# Timelapse_camera_RevB.net
KiCad netlist of a schematic drawn in EAGLE
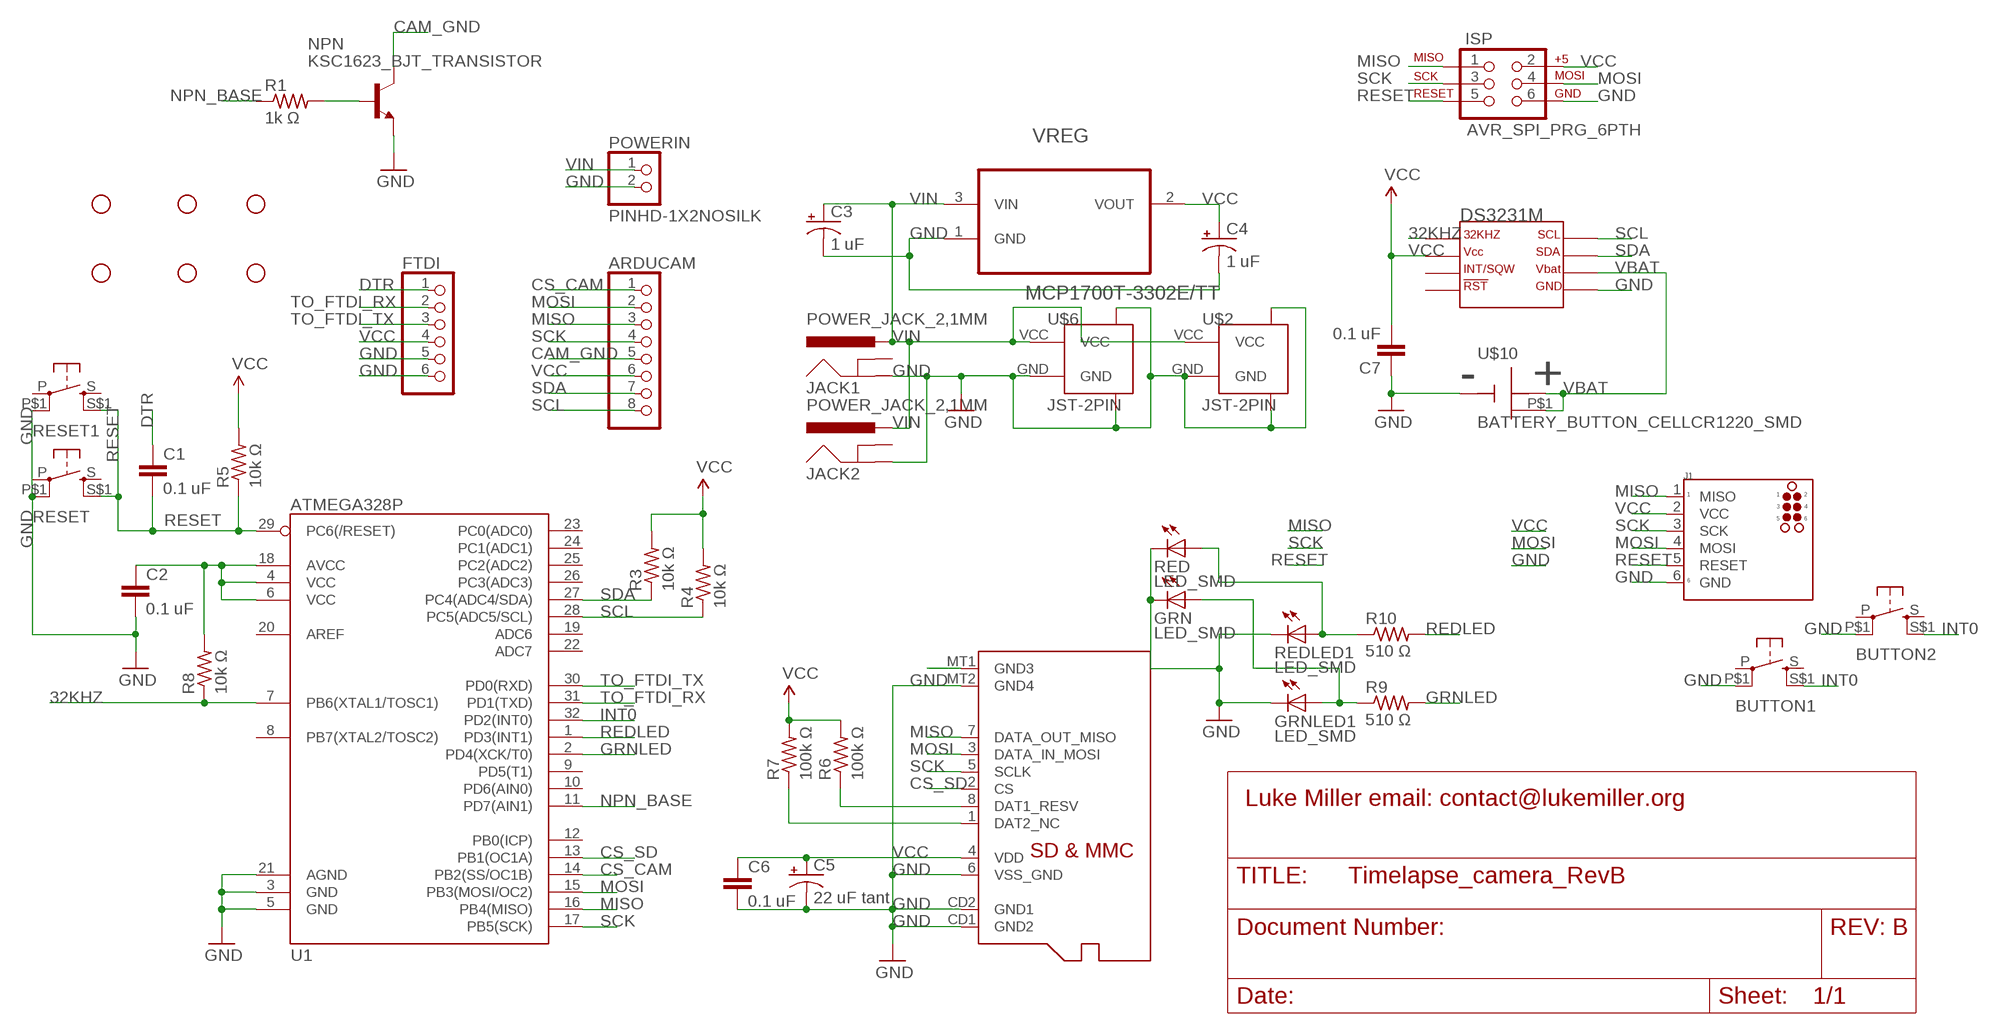
[diagram p0: schematic, sheet 1]

(export (version "E")
  (design (tool "Eeschema 10.0.6"))
  (components
    (comp (ref "ARDUCAM")
      (value "PINHD-1X8RIGHTANGLE_FEMALE")
      (footprint "eagle-import:1X08-RA")
      (libsource (lib "eagle-import") (part "PINHD-1X8RIGHTANGLE_FEMALE"))
    )
    (comp (ref "BUTTON1")
      (value "PUSHBUTTON_DPST_SMDSTANDARD")
      (footprint "eagle-import:PUSHBUTTON_DPST_SMD")
      (libsource (lib "eagle-import") (part "PUSHBUTTON_DPST_SMDSTANDARD"))
    )
    (comp (ref "BUTTON2")
      (value "PUSHBUTTON_DPST_SMDSTANDARD")
      (footprint "eagle-import:PUSHBUTTON_DPST_SMD")
      (libsource (lib "eagle-import") (part "PUSHBUTTON_DPST_SMDSTANDARD"))
    )
    (comp (ref "C1")
      (value "0.1 uF")
      (footprint "eagle-import:0805")
      (libsource (lib "eagle-import") (part "CAP0805"))
    )
    (comp (ref "C2")
      (value "0.1 uF")
      (footprint "eagle-import:0805")
      (libsource (lib "eagle-import") (part "CAP0805"))
    )
    (comp (ref "C3")
      (value "1 uF")
      (footprint "eagle-import:PANASONIC_B")
      (libsource (lib "eagle-import") (part "CPOL-USB"))
    )
    (comp (ref "C4")
      (value "1 uF")
      (footprint "eagle-import:PANASONIC_B")
      (libsource (lib "eagle-import") (part "CPOL-USB"))
    )
    (comp (ref "C5")
      (value "22 uF tant")
      (footprint "eagle-import:C0805_POL")
      (libsource (lib "eagle-import") (part "CPOL-US0805"))
    )
    (comp (ref "C6")
      (value "0.1 uF")
      (footprint "eagle-import:0805")
      (libsource (lib "eagle-import") (part "CAP0805"))
    )
    (comp (ref "C7")
      (value "0.1 uF")
      (footprint "eagle-import:0805")
      (libsource (lib "eagle-import") (part "CAP0805"))
    )
    (comp (ref "DS3231M")
      (value "DS3231MSOIC-8")
      (footprint "eagle-import:DS3231M_SOIC8")
      (libsource (lib "eagle-import") (part "DS3231MSOIC-8"))
    )
    (comp (ref "FTDI")
      (value "PINHD-1X6CB")
      (footprint "eagle-import:1X06-CLEANBIG")
      (libsource (lib "eagle-import") (part "PINHD-1X6CB"))
    )
    (comp (ref "GRN")
      (value "LED_SMD")
      (footprint "eagle-import:CHIPLED_0805")
      (libsource (lib "eagle-import") (part "LED_SMD"))
    )
    (comp (ref "GRNLED1")
      (value "LED_SMD")
      (footprint "eagle-import:CHIPLED_0805")
      (libsource (lib "eagle-import") (part "LED_SMD"))
    )
    (comp (ref "ISP")
      (value "AVR_SPI_PRG_6PTH")
      (footprint "eagle-import:2X3")
      (libsource (lib "eagle-import") (part "AVR_SPI_PRG_6PTH"))
    )
    (comp (ref "J1")
      (value "TC2030-MCP-NL")
      (footprint "eagle-import:TC2030-MCP-NL")
      (libsource (lib "eagle-import") (part "TC2030-MCP-NL"))
    )
    (comp (ref "JACK1")
      (value "POWER_JACK_2,1MM")
      (footprint "eagle-import:POWER_JACK_DC_2,1MM")
      (libsource (lib "eagle-import") (part "POWER_JACK_2,1MM"))
    )
    (comp (ref "JACK2")
      (value "POWER_JACK_2,1MM")
      (footprint "eagle-import:POWER_JACK_DC_2,1MM")
      (libsource (lib "eagle-import") (part "POWER_JACK_2,1MM"))
    )
    (comp (ref "NPN")
      (value "KSC1623_BJT_TRANSISTOR")
      (footprint "eagle-import:SOT23")
      (libsource (lib "eagle-import") (part "KSC1623_BJT_TRANSISTOR"))
    )
    (comp (ref "POWERIN")
      (value "PINHD-1X2NOSILK")
      (footprint "eagle-import:1X02_NOSILK")
      (libsource (lib "eagle-import") (part "PINHD-1X2NOSILK"))
    )
    (comp (ref "R1")
      (value "1k Ω")
      (footprint "eagle-import:R0805")
      (libsource (lib "eagle-import") (part "RESISTOR_SMDR0805"))
    )
    (comp (ref "R3")
      (value "10k Ω")
      (footprint "eagle-import:R0805")
      (libsource (lib "eagle-import") (part "RESISTOR_SMDR0805"))
    )
    (comp (ref "R4")
      (value "10k Ω")
      (footprint "eagle-import:R0805")
      (libsource (lib "eagle-import") (part "RESISTOR_SMDR0805"))
    )
    (comp (ref "R5")
      (value "10k Ω")
      (footprint "eagle-import:R0805")
      (libsource (lib "eagle-import") (part "RESISTOR_SMDR0805"))
    )
    (comp (ref "R6")
      (value "100k Ω")
      (footprint "eagle-import:R0805")
      (libsource (lib "eagle-import") (part "RESISTOR_SMDR0805"))
    )
    (comp (ref "R7")
      (value "100k Ω")
      (footprint "eagle-import:R0805")
      (libsource (lib "eagle-import") (part "RESISTOR_SMDR0805"))
    )
    (comp (ref "R8")
      (value "10k Ω")
      (footprint "eagle-import:R0805")
      (libsource (lib "eagle-import") (part "RESISTOR_SMDR0805"))
    )
    (comp (ref "R9")
      (value "510 Ω")
      (footprint "eagle-import:R0805")
      (libsource (lib "eagle-import") (part "RESISTOR_SMDR0805"))
    )
    (comp (ref "R10")
      (value "510 Ω")
      (footprint "eagle-import:R0805")
      (libsource (lib "eagle-import") (part "RESISTOR_SMDR0805"))
    )
    (comp (ref "RED")
      (value "LED_SMD")
      (footprint "eagle-import:CHIPLED_0805")
      (libsource (lib "eagle-import") (part "LED_SMD"))
    )
    (comp (ref "REDLED1")
      (value "LED_SMD")
      (footprint "eagle-import:CHIPLED_0805")
      (libsource (lib "eagle-import") (part "LED_SMD"))
    )
    (comp (ref "RESET")
      (value "PUSHBUTTON_DPST_SMDSTANDARD")
      (footprint "eagle-import:PUSHBUTTON_DPST_SMD")
      (libsource (lib "eagle-import") (part "PUSHBUTTON_DPST_SMDSTANDARD"))
    )
    (comp (ref "RESET1")
      (value "PUSHBUTTON_DPST_SMDSTANDARD")
      (footprint "eagle-import:PUSHBUTTON_DPST_SMD")
      (libsource (lib "eagle-import") (part "PUSHBUTTON_DPST_SMDSTANDARD"))
    )
    (comp (ref "STANDOFF1")
      (value "STAND-OFF")
      (footprint "eagle-import:STAND-OFF")
      (libsource (lib "eagle-import") (part "STAND-OFF"))
    )
    (comp (ref "STANDOFF2")
      (value "STAND-OFF")
      (footprint "eagle-import:STAND-OFF")
      (libsource (lib "eagle-import") (part "STAND-OFF"))
    )
    (comp (ref "STANDOFF3")
      (value "STAND-OFF")
      (footprint "eagle-import:STAND-OFF")
      (libsource (lib "eagle-import") (part "STAND-OFF"))
    )
    (comp (ref "STANDOFF4")
      (value "STAND-OFF")
      (footprint "eagle-import:STAND-OFF")
      (libsource (lib "eagle-import") (part "STAND-OFF"))
    )
    (comp (ref "STANDOFF5")
      (value "STAND-OFF")
      (footprint "eagle-import:STAND-OFF")
      (libsource (lib "eagle-import") (part "STAND-OFF"))
    )
    (comp (ref "STANDOFF6")
      (value "STAND-OFF")
      (footprint "eagle-import:STAND-OFF")
      (libsource (lib "eagle-import") (part "STAND-OFF"))
    )
    (comp (ref "U$2")
      (value "JST-2PIN")
      (footprint "eagle-import:JST-2-SMD-VERT")
      (libsource (lib "eagle-import") (part "JST-2PIN"))
    )
    (comp (ref "U$3")
      (value "MICROSD")
      (footprint "eagle-import:MICROSD")
      (libsource (lib "eagle-import") (part "MICROSD"))
    )
    (comp (ref "U$6")
      (value "JST-2PIN")
      (footprint "eagle-import:JST-2-SMD-VERT")
      (libsource (lib "eagle-import") (part "JST-2PIN"))
    )
    (comp (ref "U$10")
      (value "BATTERY_BUTTON_CELLCR1220_SMD")
      (footprint "eagle-import:CR1220_BATTERY_HOLDER_SMD")
      (libsource (lib "eagle-import") (part "BATTERY_BUTTON_CELLCR1220_SMD"))
    )
    (comp (ref "U1")
      (value "ATMEGA328P")
      (footprint "eagle-import:TQFP32-08")
      (libsource (lib "eagle-import") (part "ATMEGA328_SMT"))
    )
    (comp (ref "VREG")
      (value "MCP1700T-3302E/TT")
      (footprint "eagle-import:SOT95P237X112-3N")
      (libsource (lib "eagle-import") (part "MCP1700T-3302E/TT"))
    )
  )
  (nets
    (net (code "1") (name "/32KHZ") (class "Default")
      (node (ref "DS3231M") (pin "1") (pinfunction "P$1_32KHZ_1") (pintype "bidirectional"))
      (node (ref "R8") (pin "1") (pinfunction "1_1") (pintype "passive"))
      (node (ref "U1") (pin "7") (pinfunction "PB6(XTAL1/TOSC1)_7") (pintype "bidirectional"))
    )
    (net (code "2") (name "/CAM_GND") (class "Default")
      (node (ref "ARDUCAM") (pin "5") (pinfunction "5_5") (pintype "passive"))
      (node (ref "NPN") (pin "3") (pinfunction "C_3") (pintype "passive"))
    )
    (net (code "3") (name "/CS_CAM") (class "Default")
      (node (ref "ARDUCAM") (pin "1") (pinfunction "1_1") (pintype "passive"))
      (node (ref "U1") (pin "14") (pinfunction "PB2(SS/OC1B)_14") (pintype "bidirectional"))
    )
    (net (code "4") (name "/CS_SD") (class "Default")
      (node (ref "U$3") (pin "2") (pinfunction "CS_2") (pintype "input"))
      (node (ref "U1") (pin "13") (pinfunction "PB1(OC1A)_13") (pintype "bidirectional"))
    )
    (net (code "5") (name "/DTR") (class "Default")
      (node (ref "C1") (pin "1") (pinfunction "1_1") (pintype "passive"))
      (node (ref "FTDI") (pin "1") (pinfunction "1_1") (pintype "passive"))
    )
    (net (code "6") (name "/GRNLED") (class "Default")
      (node (ref "R9") (pin "2") (pinfunction "2_2") (pintype "passive"))
      (node (ref "U1") (pin "2") (pinfunction "PD4(XCK/T0)_2") (pintype "bidirectional"))
    )
    (net (code "7") (name "/INT0") (class "Default")
      (node (ref "BUTTON1") (pin "S$1") (pinfunction "S1_S$1") (pintype "passive"))
      (node (ref "BUTTON2") (pin "S$1") (pinfunction "S1_S$1") (pintype "passive"))
      (node (ref "U1") (pin "32") (pinfunction "PD2(INT0)_32") (pintype "bidirectional"))
    )
    (net (code "8") (name "/MISO") (class "Default")
      (node (ref "ARDUCAM") (pin "3") (pinfunction "3_3") (pintype "passive"))
      (node (ref "ISP") (pin "1") (pinfunction "1_1") (pintype "passive"))
      (node (ref "J1") (pin "1") (pinfunction "MISO_1") (pintype "bidirectional"))
      (node (ref "U$3") (pin "7") (pinfunction "DATA_OUT_MISO_7") (pintype "output"))
      (node (ref "U1") (pin "16") (pinfunction "PB4(MISO)_16") (pintype "bidirectional"))
    )
    (net (code "9") (name "/MOSI") (class "Default")
      (node (ref "ARDUCAM") (pin "2") (pinfunction "2_2") (pintype "passive"))
      (node (ref "ISP") (pin "4") (pinfunction "4_4") (pintype "passive"))
      (node (ref "J1") (pin "4") (pinfunction "MOSI_4") (pintype "bidirectional"))
      (node (ref "U$3") (pin "3") (pinfunction "DATA_IN_MOSI_3") (pintype "input"))
      (node (ref "U1") (pin "15") (pinfunction "PB3(MOSI/OC2)_15") (pintype "bidirectional"))
    )
    (net (code "10") (name "/NPN_BASE") (class "Default")
      (node (ref "R1") (pin "1") (pinfunction "1_1") (pintype "passive"))
      (node (ref "U1") (pin "11") (pinfunction "PD7(AIN1)_11") (pintype "bidirectional"))
    )
    (net (code "11") (name "/REDLED") (class "Default")
      (node (ref "R10") (pin "2") (pinfunction "2_2") (pintype "passive"))
      (node (ref "U1") (pin "1") (pinfunction "PD3(INT1)_1") (pintype "bidirectional"))
    )
    (net (code "12") (name "/RESET") (class "Default")
      (node (ref "C1") (pin "2") (pinfunction "2_2") (pintype "passive"))
      (node (ref "ISP") (pin "5") (pinfunction "5_5") (pintype "passive"))
      (node (ref "J1") (pin "5") (pinfunction "RESET_5") (pintype "bidirectional"))
      (node (ref "R5") (pin "1") (pinfunction "1_1") (pintype "passive"))
      (node (ref "RESET") (pin "S$1") (pinfunction "S1_S$1") (pintype "passive"))
      (node (ref "RESET1") (pin "S$1") (pinfunction "S1_S$1") (pintype "passive"))
      (node (ref "U1") (pin "29") (pinfunction "PC6(/RESET)_29") (pintype "bidirectional"))
    )
    (net (code "13") (name "/SCK") (class "Default")
      (node (ref "ARDUCAM") (pin "4") (pinfunction "4_4") (pintype "passive"))
      (node (ref "ISP") (pin "3") (pinfunction "3_3") (pintype "passive"))
      (node (ref "J1") (pin "3") (pinfunction "SCK_3") (pintype "bidirectional"))
      (node (ref "U$3") (pin "5") (pinfunction "SCLK_5") (pintype "input"))
      (node (ref "U1") (pin "17") (pinfunction "PB5(SCK)_17") (pintype "bidirectional"))
    )
    (net (code "14") (name "/SCL") (class "Default")
      (node (ref "ARDUCAM") (pin "8") (pinfunction "8_8") (pintype "passive"))
      (node (ref "DS3231M") (pin "8") (pinfunction "P$8_SCL_8") (pintype "bidirectional"))
      (node (ref "R4") (pin "1") (pinfunction "1_1") (pintype "passive"))
      (node (ref "U1") (pin "28") (pinfunction "PC5(ADC5/SCL)_28") (pintype "bidirectional"))
    )
    (net (code "15") (name "/SDA") (class "Default")
      (node (ref "ARDUCAM") (pin "7") (pinfunction "7_7") (pintype "passive"))
      (node (ref "DS3231M") (pin "7") (pinfunction "P$7_SDA_7") (pintype "bidirectional"))
      (node (ref "R3") (pin "1") (pinfunction "1_1") (pintype "passive"))
      (node (ref "U1") (pin "27") (pinfunction "PC4(ADC4/SDA)_27") (pintype "bidirectional"))
    )
    (net (code "16") (name "/TO_FTDI_RX") (class "Default")
      (node (ref "FTDI") (pin "2") (pinfunction "2_2") (pintype "passive"))
      (node (ref "U1") (pin "31") (pinfunction "PD1(TXD)_31") (pintype "bidirectional"))
    )
    (net (code "17") (name "/TO_FTDI_TX") (class "Default")
      (node (ref "FTDI") (pin "3") (pinfunction "3_3") (pintype "passive"))
      (node (ref "U1") (pin "30") (pinfunction "PD0(RXD)_30") (pintype "bidirectional"))
    )
    (net (code "18") (name "/VBAT") (class "Default")
      (node (ref "DS3231M") (pin "6") (pinfunction "P$6_VBAT_6") (pintype "bidirectional"))
      (node (ref "U$10") (pin "P$1") (pinfunction "P$2_VBAT_P$1") (pintype "power_in"))
      (node (ref "U$10") (pin "P$2") (pinfunction "VBAT_P$2") (pintype "power_in"))
    )
    (net (code "19") (name "/VIN") (class "Default")
      (node (ref "C3") (pin "+") (pinfunction "+_+") (pintype "passive"))
      (node (ref "JACK1") (pin "P$1") (pinfunction "PWR_P$1") (pintype "bidirectional"))
      (node (ref "JACK2") (pin "P$1") (pinfunction "PWR_P$1") (pintype "bidirectional"))
      (node (ref "POWERIN") (pin "1") (pinfunction "1_1") (pintype "passive"))
      (node (ref "U$2") (pin "VCC") (pinfunction "VCC_VCC") (pintype "power_in"))
      (node (ref "U$6") (pin "VCC") (pinfunction "VCC_VCC") (pintype "power_in"))
      (node (ref "VREG") (pin "3") (pinfunction "VIN_3") (pintype "input"))
    )
    (net (code "20") (name "GND") (class "Default")
      (node (ref "BUTTON1") (pin "P$1") (pinfunction "P1_P$1") (pintype "passive"))
      (node (ref "BUTTON2") (pin "P$1") (pinfunction "P1_P$1") (pintype "passive"))
      (node (ref "C2") (pin "2") (pinfunction "2_2") (pintype "passive"))
      (node (ref "C3") (pin "-") (pinfunction "-_-") (pintype "passive"))
      (node (ref "C4") (pin "-") (pinfunction "-_-") (pintype "passive"))
      (node (ref "C5") (pin "P$2_C") (pinfunction "-_P$2_C") (pintype "passive"))
      (node (ref "C6") (pin "2") (pinfunction "2_2") (pintype "passive"))
      (node (ref "C7") (pin "1") (pinfunction "1_1") (pintype "passive"))
      (node (ref "DS3231M") (pin "5") (pinfunction "P$5_GND_5") (pintype "power_in"))
      (node (ref "FTDI") (pin "5") (pinfunction "5_5") (pintype "passive"))
      (node (ref "FTDI") (pin "6") (pinfunction "6_6") (pintype "passive"))
      (node (ref "GRN") (pin "C") (pinfunction "C_C") (pintype "passive"))
      (node (ref "GRNLED1") (pin "C") (pinfunction "C_C") (pintype "passive"))
      (node (ref "ISP") (pin "6") (pinfunction "6_6") (pintype "passive"))
      (node (ref "J1") (pin "6") (pinfunction "GND_6") (pintype "power_in"))
      (node (ref "JACK1") (pin "P$2") (pinfunction "GND_P$2") (pintype "bidirectional"))
      (node (ref "JACK2") (pin "P$2") (pinfunction "GND_P$2") (pintype "bidirectional"))
      (node (ref "NPN") (pin "2") (pinfunction "E_2") (pintype "passive"))
      (node (ref "POWERIN") (pin "2") (pinfunction "2_2") (pintype "passive"))
      (node (ref "RED") (pin "C") (pinfunction "C_C") (pintype "passive"))
      (node (ref "REDLED1") (pin "C") (pinfunction "C_C") (pintype "passive"))
      (node (ref "RESET") (pin "P$1") (pinfunction "P1_P$1") (pintype "passive"))
      (node (ref "RESET1") (pin "P$1") (pinfunction "P1_P$1") (pintype "passive"))
      (node (ref "U$10") (pin "GND") (pinfunction "GND_GND") (pintype "power_in"))
      (node (ref "U$2") (pin "GND") (pinfunction "GND_GND") (pintype "power_in"))
      (node (ref "U$2") (pin "P$1") (pinfunction "BODY1_P$1") (pintype "power_in"))
      (node (ref "U$2") (pin "P$2") (pinfunction "BODY2_P$2") (pintype "power_in"))
      (node (ref "U$3") (pin "6") (pinfunction "VSS_GND_6") (pintype "power_in"))
      (node (ref "U$3") (pin "CD1") (pinfunction "GND2_CD1") (pintype "power_in"))
      (node (ref "U$3") (pin "CD2") (pinfunction "GND1_CD2") (pintype "power_in"))
      (node (ref "U$3") (pin "MT2") (pinfunction "GND4_MT2") (pintype "passive"))
      (node (ref "U$6") (pin "GND") (pinfunction "GND_GND") (pintype "power_in"))
      (node (ref "U$6") (pin "P$1") (pinfunction "BODY1_P$1") (pintype "power_in"))
      (node (ref "U$6") (pin "P$2") (pinfunction "BODY2_P$2") (pintype "power_in"))
      (node (ref "U1") (pin "21") (pinfunction "AGND_21") (pintype "bidirectional"))
      (node (ref "U1") (pin "3") (pinfunction "GND_3") (pintype "bidirectional"))
      (node (ref "U1") (pin "5") (pinfunction "GND_5") (pintype "bidirectional"))
      (node (ref "VREG") (pin "1") (pinfunction "GND_1") (pintype "passive"))
    )
    (net (code "21") (name "Net-(GRN-PadA)") (class "Default")
      (node (ref "GRN") (pin "A") (pinfunction "A_A") (pintype "passive"))
      (node (ref "GRNLED1") (pin "A") (pinfunction "A_A") (pintype "passive"))
      (node (ref "R9") (pin "1") (pinfunction "1_1") (pintype "passive"))
    )
    (net (code "22") (name "Net-(NPN-B)") (class "Default")
      (node (ref "NPN") (pin "1") (pinfunction "B_1") (pintype "passive"))
      (node (ref "R1") (pin "2") (pinfunction "2_2") (pintype "passive"))
    )
    (net (code "23") (name "Net-(R10-Pad1)") (class "Default")
      (node (ref "R10") (pin "1") (pinfunction "1_1") (pintype "passive"))
      (node (ref "RED") (pin "A") (pinfunction "A_A") (pintype "passive"))
      (node (ref "REDLED1") (pin "A") (pinfunction "A_A") (pintype "passive"))
    )
    (net (code "24") (name "Net-(U$3-DAT1_RESV)") (class "Default")
      (node (ref "R6") (pin "1") (pinfunction "1_1") (pintype "passive"))
      (node (ref "U$3") (pin "8") (pinfunction "DAT1_RESV_8") (pintype "bidirectional"))
    )
    (net (code "25") (name "Net-(U$3-DAT2_NC)") (class "Default")
      (node (ref "R7") (pin "1") (pinfunction "1_1") (pintype "passive"))
      (node (ref "U$3") (pin "1") (pinfunction "DAT2_NC_1") (pintype "bidirectional"))
    )
    (net (code "26") (name "VCC") (class "Default")
      (node (ref "ARDUCAM") (pin "6") (pinfunction "6_6") (pintype "passive"))
      (node (ref "C2") (pin "1") (pinfunction "1_1") (pintype "passive"))
      (node (ref "C4") (pin "+") (pinfunction "+_+") (pintype "passive"))
      (node (ref "C5") (pin "P$1_A") (pinfunction "+_P$1_A") (pintype "passive"))
      (node (ref "C6") (pin "1") (pinfunction "1_1") (pintype "passive"))
      (node (ref "C7") (pin "2") (pinfunction "2_2") (pintype "passive"))
      (node (ref "DS3231M") (pin "2") (pinfunction "P$2_VCC_2") (pintype "power_in"))
      (node (ref "FTDI") (pin "4") (pinfunction "4_4") (pintype "passive"))
      (node (ref "ISP") (pin "2") (pinfunction "2_2") (pintype "passive"))
      (node (ref "J1") (pin "2") (pinfunction "VCC_2") (pintype "power_in"))
      (node (ref "R3") (pin "2") (pinfunction "2_2") (pintype "passive"))
      (node (ref "R4") (pin "2") (pinfunction "2_2") (pintype "passive"))
      (node (ref "R5") (pin "2") (pinfunction "2_2") (pintype "passive"))
      (node (ref "R6") (pin "2") (pinfunction "2_2") (pintype "passive"))
      (node (ref "R7") (pin "2") (pinfunction "2_2") (pintype "passive"))
      (node (ref "R8") (pin "2") (pinfunction "2_2") (pintype "passive"))
      (node (ref "U$3") (pin "4") (pinfunction "VDD_4") (pintype "power_in"))
      (node (ref "U1") (pin "18") (pinfunction "AVCC_18") (pintype "bidirectional"))
      (node (ref "U1") (pin "4") (pinfunction "VCC_4") (pintype "bidirectional"))
      (node (ref "U1") (pin "6") (pinfunction "VCC_6") (pintype "bidirectional"))
      (node (ref "VREG") (pin "2") (pinfunction "VOUT_2") (pintype "output"))
    )
    (net (code "27") (name "unconnected-(BUTTON1-PadP)") (class "Default")
      (node (ref "BUTTON1") (pin "P") (pinfunction "P_P") (pintype "passive"))
    )
    (net (code "28") (name "unconnected-(BUTTON1-PadS)") (class "Default")
      (node (ref "BUTTON1") (pin "S") (pinfunction "S_S") (pintype "passive"))
    )
    (net (code "29") (name "unconnected-(BUTTON2-PadP)") (class "Default")
      (node (ref "BUTTON2") (pin "P") (pinfunction "P_P") (pintype "passive"))
    )
    (net (code "30") (name "unconnected-(BUTTON2-PadS)") (class "Default")
      (node (ref "BUTTON2") (pin "S") (pinfunction "S_S") (pintype "passive"))
    )
    (net (code "31") (name "unconnected-(DS3231M-P$3_INT-Pad3)") (class "Default")
      (node (ref "DS3231M") (pin "3") (pinfunction "P$3_INT_3") (pintype "bidirectional"))
    )
    (net (code "32") (name "unconnected-(DS3231M-P$4_RST-Pad4)") (class "Default")
      (node (ref "DS3231M") (pin "4") (pinfunction "P$4_RST_4") (pintype "bidirectional"))
    )
    (net (code "33") (name "unconnected-(JACK1-GNDBREAK-PadP$3)") (class "Default")
      (node (ref "JACK1") (pin "P$3") (pinfunction "GNDBREAK_P$3") (pintype "bidirectional"))
    )
    (net (code "34") (name "unconnected-(JACK2-GNDBREAK-PadP$3)") (class "Default")
      (node (ref "JACK2") (pin "P$3") (pinfunction "GNDBREAK_P$3") (pintype "bidirectional"))
    )
    (net (code "35") (name "unconnected-(RESET-PadP)") (class "Default")
      (node (ref "RESET") (pin "P") (pinfunction "P_P") (pintype "passive"))
    )
    (net (code "36") (name "unconnected-(RESET-PadS)") (class "Default")
      (node (ref "RESET") (pin "S") (pinfunction "S_S") (pintype "passive"))
    )
    (net (code "37") (name "unconnected-(RESET1-PadP)") (class "Default")
      (node (ref "RESET1") (pin "P") (pinfunction "P_P") (pintype "passive"))
    )
    (net (code "38") (name "unconnected-(RESET1-PadS)") (class "Default")
      (node (ref "RESET1") (pin "S") (pinfunction "S_S") (pintype "passive"))
    )
    (net (code "39") (name "unconnected-(U$3-GND3-PadMT1)") (class "Default")
      (node (ref "U$3") (pin "MT1") (pinfunction "GND3_MT1") (pintype "passive"))
    )
    (net (code "40") (name "unconnected-(U1-ADC6-Pad19)") (class "Default")
      (node (ref "U1") (pin "19") (pinfunction "ADC6_19") (pintype "bidirectional"))
    )
    (net (code "41") (name "unconnected-(U1-ADC7-Pad22)") (class "Default")
      (node (ref "U1") (pin "22") (pinfunction "ADC7_22") (pintype "bidirectional"))
    )
    (net (code "42") (name "unconnected-(U1-AREF-Pad20)") (class "Default")
      (node (ref "U1") (pin "20") (pinfunction "AREF_20") (pintype "bidirectional"))
    )
    (net (code "43") (name "unconnected-(U1-PB0(ICP)-Pad12)") (class "Default")
      (node (ref "U1") (pin "12") (pinfunction "PB0(ICP)_12") (pintype "bidirectional"))
    )
    (net (code "44") (name "unconnected-(U1-PB7(XTAL2{slash}TOSC2)-Pad8)") (class "Default")
      (node (ref "U1") (pin "8") (pinfunction "PB7(XTAL2/TOSC2)_8") (pintype "bidirectional"))
    )
    (net (code "45") (name "unconnected-(U1-PC0(ADC0)-Pad23)") (class "Default")
      (node (ref "U1") (pin "23") (pinfunction "PC0(ADC0)_23") (pintype "bidirectional"))
    )
    (net (code "46") (name "unconnected-(U1-PC1(ADC1)-Pad24)") (class "Default")
      (node (ref "U1") (pin "24") (pinfunction "PC1(ADC1)_24") (pintype "bidirectional"))
    )
    (net (code "47") (name "unconnected-(U1-PC2(ADC2)-Pad25)") (class "Default")
      (node (ref "U1") (pin "25") (pinfunction "PC2(ADC2)_25") (pintype "bidirectional"))
    )
    (net (code "48") (name "unconnected-(U1-PC3(ADC3)-Pad26)") (class "Default")
      (node (ref "U1") (pin "26") (pinfunction "PC3(ADC3)_26") (pintype "bidirectional"))
    )
    (net (code "49") (name "unconnected-(U1-PD5(T1)-Pad9)") (class "Default")
      (node (ref "U1") (pin "9") (pinfunction "PD5(T1)_9") (pintype "bidirectional"))
    )
    (net (code "50") (name "unconnected-(U1-PD6(AIN0)-Pad10)") (class "Default")
      (node (ref "U1") (pin "10") (pinfunction "PD6(AIN0)_10") (pintype "bidirectional"))
    )
  )
)
